# IRSensorController.net
KiCad netlist of a schematic drawn in EAGLE
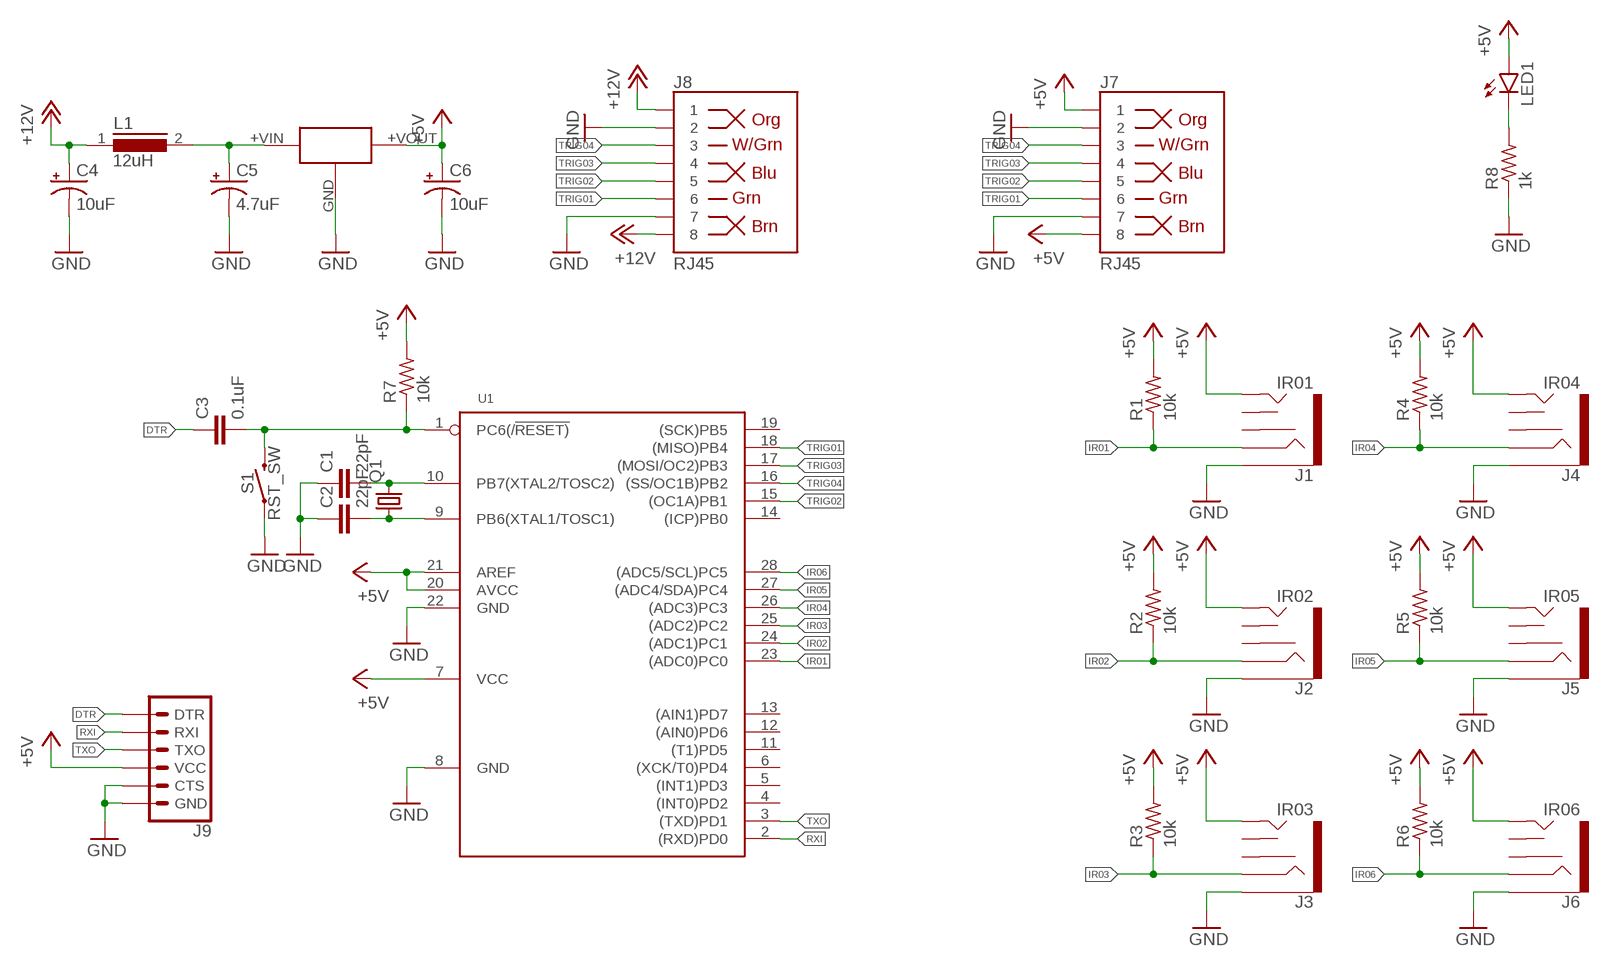
[diagram p0: schematic, sheet 1]

(export (version "E")
  (design (tool "Eeschema 10.0.6"))
  (components
    (comp (ref "C1")
      (value "22pF")
      (footprint "eagle-import:C050-025X075")
      (libsource (lib "eagle-import") (part "C-EU050-025X075"))
    )
    (comp (ref "C2")
      (value "22pF")
      (footprint "eagle-import:C050-025X075")
      (libsource (lib "eagle-import") (part "C-EU050-025X075"))
    )
    (comp (ref "C3")
      (value "0.1uF")
      (footprint "eagle-import:C050-025X075")
      (libsource (lib "eagle-import") (part "C-EU050-025X075"))
    )
    (comp (ref "C4")
      (value "10uF")
      (footprint "eagle-import:E3,5-8")
      (libsource (lib "eagle-import") (part "CPOL-USE3.5-8"))
    )
    (comp (ref "C5")
      (value "4.7uF")
      (footprint "eagle-import:E2,5-7")
      (libsource (lib "eagle-import") (part "CPOL-USE2.5-7"))
    )
    (comp (ref "C6")
      (value "10uF")
      (footprint "eagle-import:E3,5-8")
      (libsource (lib "eagle-import") (part "CPOL-USE3.5-8"))
    )
    (comp (ref "J1")
      (value "IR01")
      (footprint "eagle-import:AUDIO-JACK-KIT")
      (libsource (lib "eagle-import") (part "AUDIO_JACK_3.5MM_KIT"))
    )
    (comp (ref "J2")
      (value "IR02")
      (footprint "eagle-import:AUDIO-JACK-KIT")
      (libsource (lib "eagle-import") (part "AUDIO_JACK_3.5MM_KIT"))
    )
    (comp (ref "J3")
      (value "IR03")
      (footprint "eagle-import:AUDIO-JACK-KIT")
      (libsource (lib "eagle-import") (part "AUDIO_JACK_3.5MM_KIT"))
    )
    (comp (ref "J4")
      (value "IR04")
      (footprint "eagle-import:AUDIO-JACK-KIT")
      (libsource (lib "eagle-import") (part "AUDIO_JACK_3.5MM_KIT"))
    )
    (comp (ref "J5")
      (value "IR05")
      (footprint "eagle-import:AUDIO-JACK-KIT")
      (libsource (lib "eagle-import") (part "AUDIO_JACK_3.5MM_KIT"))
    )
    (comp (ref "J6")
      (value "IR06")
      (footprint "eagle-import:AUDIO-JACK-KIT")
      (libsource (lib "eagle-import") (part "AUDIO_JACK_3.5MM_KIT"))
    )
    (comp (ref "J7")
      (value "RJ45")
      (footprint "eagle-import:RJ45-8")
      (libsource (lib "eagle-import") (part "RJ45-8"))
    )
    (comp (ref "J8")
      (value "RJ45")
      (footprint "eagle-import:RJ45-8")
      (libsource (lib "eagle-import") (part "RJ45-8"))
    )
    (comp (ref "J9")
      (value "6_PIN_SERIAL_TARGETSILK")
      (footprint "eagle-import:6_PIN_SERIAL_TARGET_SIDE_W_SILK")
      (libsource (lib "eagle-import") (part "6_PIN_SERIAL_TARGETSILK"))
    )
    (comp (ref "L1")
      (value "12uH")
      (footprint "eagle-import:SUKW1-17")
      (libsource (lib "eagle-import") (part "B82131"))
    )
    (comp (ref "LED1")
      (value "LED5MM")
      (footprint "eagle-import:LED5MM")
      (libsource (lib "eagle-import") (part "LED5MM"))
    )
    (comp (ref "Q1")
      (value "CRYSTALHC49S")
      (footprint "eagle-import:HC49_S")
      (libsource (lib "eagle-import") (part "CRYSTALHC49S"))
    )
    (comp (ref "R1")
      (value "10k")
      (footprint "eagle-import:0204_7")
      (libsource (lib "eagle-import") (part "R-US_0204/7"))
    )
    (comp (ref "R2")
      (value "10k")
      (footprint "eagle-import:0204_7")
      (libsource (lib "eagle-import") (part "R-US_0204/7"))
    )
    (comp (ref "R3")
      (value "10k")
      (footprint "eagle-import:0204_7")
      (libsource (lib "eagle-import") (part "R-US_0204/7"))
    )
    (comp (ref "R4")
      (value "10k")
      (footprint "eagle-import:0204_7")
      (libsource (lib "eagle-import") (part "R-US_0204/7"))
    )
    (comp (ref "R5")
      (value "10k")
      (footprint "eagle-import:0204_7")
      (libsource (lib "eagle-import") (part "R-US_0204/7"))
    )
    (comp (ref "R6")
      (value "10k")
      (footprint "eagle-import:0204_7")
      (libsource (lib "eagle-import") (part "R-US_0204/7"))
    )
    (comp (ref "R7")
      (value "10k")
      (footprint "eagle-import:0204_7")
      (libsource (lib "eagle-import") (part "R-US_0204/7"))
    )
    (comp (ref "R8")
      (value "1k")
      (footprint "eagle-import:0204_7")
      (libsource (lib "eagle-import") (part "R-US_0204/7"))
    )
    (comp (ref "S1")
      (value "RST_SW")
      (footprint "eagle-import:TACTILE_SWITCH_PTH_6.0MM")
      (libsource (lib "eagle-import") (part "MOMENTARY-SWITCH-SPST-PTH-6.0MM"))
    )
    (comp (ref "U$1")
      (value "R_78E_5V")
      (footprint "eagle-import:R_78E")
      (libsource (lib "eagle-import") (part "R_78E_5V"))
    )
    (comp (ref "U1")
      (value "MCU-ATMEGA328P-PU(DIP28)")
      (footprint "eagle-import:DIP28-2.54-34.7X7.62MM")
      (fields (field (name "MPN") "ATMEGA328P-PU"))
      (libsource (lib "eagle-import") (part "MCU-ATMEGA328P-PU(DIP28)"))
    )
  )
  (nets
    (net (code "1") (name "+5V") (class "Default")
      (node (ref "C6") (pin "+") (pinfunction "+_+") (pintype "passive"))
      (node (ref "J1") (pin "TIP") (pinfunction "TIP_TIP") (pintype "bidirectional"))
      (node (ref "J2") (pin "TIP") (pinfunction "TIP_TIP") (pintype "bidirectional"))
      (node (ref "J3") (pin "TIP") (pinfunction "TIP_TIP") (pintype "bidirectional"))
      (node (ref "J4") (pin "TIP") (pinfunction "TIP_TIP") (pintype "bidirectional"))
      (node (ref "J5") (pin "TIP") (pinfunction "TIP_TIP") (pintype "bidirectional"))
      (node (ref "J6") (pin "TIP") (pinfunction "TIP_TIP") (pintype "bidirectional"))
      (node (ref "J7") (pin "1") (pinfunction "1_1") (pintype "bidirectional"))
      (node (ref "J7") (pin "8") (pinfunction "8_8") (pintype "bidirectional"))
      (node (ref "J9") (pin "P$4") (pinfunction "VCC_P$4") (pintype "passive"))
      (node (ref "LED1") (pin "A") (pinfunction "A_A") (pintype "passive"))
      (node (ref "R1") (pin "2") (pinfunction "2_2") (pintype "passive"))
      (node (ref "R2") (pin "2") (pinfunction "2_2") (pintype "passive"))
      (node (ref "R3") (pin "2") (pinfunction "2_2") (pintype "passive"))
      (node (ref "R4") (pin "2") (pinfunction "2_2") (pintype "passive"))
      (node (ref "R5") (pin "2") (pinfunction "2_2") (pintype "passive"))
      (node (ref "R6") (pin "2") (pinfunction "2_2") (pintype "passive"))
      (node (ref "R7") (pin "2") (pinfunction "2_2") (pintype "passive"))
      (node (ref "U$1") (pin "+VOUT") (pinfunction "+VOUT_+VOUT") (pintype "bidirectional"))
      (node (ref "U1") (pin "20") (pinfunction "AVCC_20") (pintype "bidirectional"))
      (node (ref "U1") (pin "21") (pinfunction "AREF_21") (pintype "bidirectional"))
      (node (ref "U1") (pin "7") (pinfunction "VCC_7") (pintype "bidirectional"))
    )
    (net (code "2") (name "+12V") (class "Default")
      (node (ref "C4") (pin "+") (pinfunction "+_+") (pintype "passive"))
      (node (ref "J8") (pin "1") (pinfunction "1_1") (pintype "bidirectional"))
      (node (ref "J8") (pin "8") (pinfunction "8_8") (pintype "bidirectional"))
      (node (ref "L1") (pin "1") (pinfunction "1_1") (pintype "passive"))
    )
    (net (code "3") (name "DTR") (class "Default")
      (node (ref "C3") (pin "1") (pinfunction "1_1") (pintype "passive"))
      (node (ref "J9") (pin "P$1") (pinfunction "DTR_P$1") (pintype "passive"))
    )
    (net (code "4") (name "GND") (class "Default")
      (node (ref "C1") (pin "1") (pinfunction "1_1") (pintype "passive"))
      (node (ref "C2") (pin "1") (pinfunction "1_1") (pintype "passive"))
      (node (ref "C4") (pin "-") (pinfunction "-_-") (pintype "passive"))
      (node (ref "C5") (pin "-") (pinfunction "-_-") (pintype "passive"))
      (node (ref "C6") (pin "-") (pinfunction "-_-") (pintype "passive"))
      (node (ref "J1") (pin "SLEEVE") (pinfunction "SLEEVE_SLEEVE") (pintype "bidirectional"))
      (node (ref "J2") (pin "SLEEVE") (pinfunction "SLEEVE_SLEEVE") (pintype "bidirectional"))
      (node (ref "J3") (pin "SLEEVE") (pinfunction "SLEEVE_SLEEVE") (pintype "bidirectional"))
      (node (ref "J4") (pin "SLEEVE") (pinfunction "SLEEVE_SLEEVE") (pintype "bidirectional"))
      (node (ref "J5") (pin "SLEEVE") (pinfunction "SLEEVE_SLEEVE") (pintype "bidirectional"))
      (node (ref "J6") (pin "SLEEVE") (pinfunction "SLEEVE_SLEEVE") (pintype "bidirectional"))
      (node (ref "J7") (pin "2") (pinfunction "2_2") (pintype "bidirectional"))
      (node (ref "J7") (pin "7") (pinfunction "7_7") (pintype "bidirectional"))
      (node (ref "J8") (pin "2") (pinfunction "2_2") (pintype "bidirectional"))
      (node (ref "J8") (pin "7") (pinfunction "7_7") (pintype "bidirectional"))
      (node (ref "J9") (pin "P$5") (pinfunction "CTS_P$5") (pintype "passive"))
      (node (ref "J9") (pin "P$6") (pinfunction "GND_P$6") (pintype "passive"))
      (node (ref "R8") (pin "1") (pinfunction "1_1") (pintype "passive"))
      (node (ref "S1") (pin "1") (pinfunction "1_1") (pintype "passive"))
      (node (ref "U$1") (pin "GND") (pinfunction "GND_GND") (pintype "bidirectional"))
      (node (ref "U1") (pin "22") (pinfunction "GND_22") (pintype "bidirectional"))
      (node (ref "U1") (pin "8") (pinfunction "GND_8") (pintype "bidirectional"))
    )
    (net (code "5") (name "IR01") (class "Default")
      (node (ref "J1") (pin "RING") (pinfunction "RING_RING") (pintype "bidirectional"))
      (node (ref "R1") (pin "1") (pinfunction "1_1") (pintype "passive"))
      (node (ref "U1") (pin "23") (pinfunction "(ADC0)PC0_23") (pintype "bidirectional"))
    )
    (net (code "6") (name "IR02") (class "Default")
      (node (ref "J2") (pin "RING") (pinfunction "RING_RING") (pintype "bidirectional"))
      (node (ref "R2") (pin "1") (pinfunction "1_1") (pintype "passive"))
      (node (ref "U1") (pin "24") (pinfunction "(ADC1)PC1_24") (pintype "bidirectional"))
    )
    (net (code "7") (name "IR03") (class "Default")
      (node (ref "J3") (pin "RING") (pinfunction "RING_RING") (pintype "bidirectional"))
      (node (ref "R3") (pin "1") (pinfunction "1_1") (pintype "passive"))
      (node (ref "U1") (pin "25") (pinfunction "(ADC2)PC2_25") (pintype "bidirectional"))
    )
    (net (code "8") (name "IR04") (class "Default")
      (node (ref "J4") (pin "RING") (pinfunction "RING_RING") (pintype "bidirectional"))
      (node (ref "R4") (pin "1") (pinfunction "1_1") (pintype "passive"))
      (node (ref "U1") (pin "26") (pinfunction "(ADC3)PC3_26") (pintype "bidirectional"))
    )
    (net (code "9") (name "IR05") (class "Default")
      (node (ref "J5") (pin "RING") (pinfunction "RING_RING") (pintype "bidirectional"))
      (node (ref "R5") (pin "1") (pinfunction "1_1") (pintype "passive"))
      (node (ref "U1") (pin "27") (pinfunction "(ADC4/SDA)PC4_27") (pintype "bidirectional"))
    )
    (net (code "10") (name "IR06") (class "Default")
      (node (ref "J6") (pin "RING") (pinfunction "RING_RING") (pintype "bidirectional"))
      (node (ref "R6") (pin "1") (pinfunction "1_1") (pintype "passive"))
      (node (ref "U1") (pin "28") (pinfunction "(ADC5/SCL)PC5_28") (pintype "bidirectional"))
    )
    (net (code "11") (name "Net-(C5-Pad+)") (class "Default")
      (node (ref "C5") (pin "+") (pinfunction "+_+") (pintype "passive"))
      (node (ref "L1") (pin "2") (pinfunction "2_2") (pintype "passive"))
      (node (ref "U$1") (pin "+VIN") (pinfunction "+VIN_+VIN") (pintype "bidirectional"))
    )
    (net (code "12") (name "Net-(LED1-C)") (class "Default")
      (node (ref "LED1") (pin "K") (pinfunction "C_K") (pintype "passive"))
      (node (ref "R8") (pin "2") (pinfunction "2_2") (pintype "passive"))
    )
    (net (code "13") (name "Net-(S1-2)") (class "Default")
      (node (ref "C3") (pin "2") (pinfunction "2_2") (pintype "passive"))
      (node (ref "R7") (pin "1") (pinfunction "1_1") (pintype "passive"))
      (node (ref "S1") (pin "3") (pinfunction "2_3") (pintype "passive"))
      (node (ref "U1") (pin "1") (pinfunction "PC6(/~{RESET})_1") (pintype "bidirectional"))
    )
    (net (code "14") (name "Net-(U1-PB6(XTAL1{slash}TOSC1))") (class "Default")
      (node (ref "C2") (pin "2") (pinfunction "2_2") (pintype "passive"))
      (node (ref "Q1") (pin "1") (pinfunction "1_1") (pintype "passive"))
      (node (ref "U1") (pin "9") (pinfunction "PB6(XTAL1/TOSC1)_9") (pintype "bidirectional"))
    )
    (net (code "15") (name "Net-(U1-PB7(XTAL2{slash}TOSC2))") (class "Default")
      (node (ref "C1") (pin "2") (pinfunction "2_2") (pintype "passive"))
      (node (ref "Q1") (pin "2") (pinfunction "2_2") (pintype "passive"))
      (node (ref "U1") (pin "10") (pinfunction "PB7(XTAL2/TOSC2)_10") (pintype "bidirectional"))
    )
    (net (code "16") (name "RXI") (class "Default")
      (node (ref "J9") (pin "P$3") (pinfunction "RXI_P$3") (pintype "passive"))
      (node (ref "U1") (pin "2") (pinfunction "(RXD)PD0_2") (pintype "bidirectional"))
    )
    (net (code "17") (name "TRIG01") (class "Default")
      (node (ref "J7") (pin "6") (pinfunction "6_6") (pintype "bidirectional"))
      (node (ref "J8") (pin "6") (pinfunction "6_6") (pintype "bidirectional"))
      (node (ref "U1") (pin "18") (pinfunction "(MISO)PB4_18") (pintype "bidirectional"))
    )
    (net (code "18") (name "TRIG02") (class "Default")
      (node (ref "J7") (pin "5") (pinfunction "5_5") (pintype "bidirectional"))
      (node (ref "J8") (pin "5") (pinfunction "5_5") (pintype "bidirectional"))
      (node (ref "U1") (pin "15") (pinfunction "(OC1A)PB1_15") (pintype "bidirectional"))
    )
    (net (code "19") (name "TRIG03") (class "Default")
      (node (ref "J7") (pin "4") (pinfunction "4_4") (pintype "bidirectional"))
      (node (ref "J8") (pin "4") (pinfunction "4_4") (pintype "bidirectional"))
      (node (ref "U1") (pin "17") (pinfunction "(MOSI/OC2)PB3_17") (pintype "bidirectional"))
    )
    (net (code "20") (name "TRIG04") (class "Default")
      (node (ref "J7") (pin "3") (pinfunction "3_3") (pintype "bidirectional"))
      (node (ref "J8") (pin "3") (pinfunction "3_3") (pintype "bidirectional"))
      (node (ref "U1") (pin "16") (pinfunction "(SS/OC1B)PB2_16") (pintype "bidirectional"))
    )
    (net (code "21") (name "TXO") (class "Default")
      (node (ref "J9") (pin "P$2") (pinfunction "TXO_P$2") (pintype "passive"))
      (node (ref "U1") (pin "3") (pinfunction "(TXD)PD1_3") (pintype "bidirectional"))
    )
    (net (code "22") (name "unconnected-(J1-PadRSH)") (class "Default")
      (node (ref "J1") (pin "RSH") (pinfunction "RSH_RSH") (pintype "bidirectional"))
    )
    (net (code "23") (name "unconnected-(J1-PadTSH)") (class "Default")
      (node (ref "J1") (pin "TSH") (pinfunction "TSH_TSH") (pintype "bidirectional"))
    )
    (net (code "24") (name "unconnected-(J2-PadRSH)") (class "Default")
      (node (ref "J2") (pin "RSH") (pinfunction "RSH_RSH") (pintype "bidirectional"))
    )
    (net (code "25") (name "unconnected-(J2-PadTSH)") (class "Default")
      (node (ref "J2") (pin "TSH") (pinfunction "TSH_TSH") (pintype "bidirectional"))
    )
    (net (code "26") (name "unconnected-(J3-PadRSH)") (class "Default")
      (node (ref "J3") (pin "RSH") (pinfunction "RSH_RSH") (pintype "bidirectional"))
    )
    (net (code "27") (name "unconnected-(J3-PadTSH)") (class "Default")
      (node (ref "J3") (pin "TSH") (pinfunction "TSH_TSH") (pintype "bidirectional"))
    )
    (net (code "28") (name "unconnected-(J4-PadRSH)") (class "Default")
      (node (ref "J4") (pin "RSH") (pinfunction "RSH_RSH") (pintype "bidirectional"))
    )
    (net (code "29") (name "unconnected-(J4-PadTSH)") (class "Default")
      (node (ref "J4") (pin "TSH") (pinfunction "TSH_TSH") (pintype "bidirectional"))
    )
    (net (code "30") (name "unconnected-(J5-PadRSH)") (class "Default")
      (node (ref "J5") (pin "RSH") (pinfunction "RSH_RSH") (pintype "bidirectional"))
    )
    (net (code "31") (name "unconnected-(J5-PadTSH)") (class "Default")
      (node (ref "J5") (pin "TSH") (pinfunction "TSH_TSH") (pintype "bidirectional"))
    )
    (net (code "32") (name "unconnected-(J6-PadRSH)") (class "Default")
      (node (ref "J6") (pin "RSH") (pinfunction "RSH_RSH") (pintype "bidirectional"))
    )
    (net (code "33") (name "unconnected-(J6-PadTSH)") (class "Default")
      (node (ref "J6") (pin "TSH") (pinfunction "TSH_TSH") (pintype "bidirectional"))
    )
    (net (code "34") (name "unconnected-(U1-(AIN0)PD6-Pad12)") (class "Default")
      (node (ref "U1") (pin "12") (pinfunction "(AIN0)PD6_12") (pintype "bidirectional"))
    )
    (net (code "35") (name "unconnected-(U1-(AIN1)PD7-Pad13)") (class "Default")
      (node (ref "U1") (pin "13") (pinfunction "(AIN1)PD7_13") (pintype "bidirectional"))
    )
    (net (code "36") (name "unconnected-(U1-(ICP)PB0-Pad14)") (class "Default")
      (node (ref "U1") (pin "14") (pinfunction "(ICP)PB0_14") (pintype "bidirectional"))
    )
    (net (code "37") (name "unconnected-(U1-(INT0)PD2-Pad4)") (class "Default")
      (node (ref "U1") (pin "4") (pinfunction "(INT0)PD2_4") (pintype "bidirectional"))
    )
    (net (code "38") (name "unconnected-(U1-(INT1)PD3-Pad5)") (class "Default")
      (node (ref "U1") (pin "5") (pinfunction "(INT1)PD3_5") (pintype "bidirectional"))
    )
    (net (code "39") (name "unconnected-(U1-(SCK)PB5-Pad19)") (class "Default")
      (node (ref "U1") (pin "19") (pinfunction "(SCK)PB5_19") (pintype "bidirectional"))
    )
    (net (code "40") (name "unconnected-(U1-(T1)PD5-Pad11)") (class "Default")
      (node (ref "U1") (pin "11") (pinfunction "(T1)PD5_11") (pintype "bidirectional"))
    )
    (net (code "41") (name "unconnected-(U1-(XCK{slash}T0)PD4-Pad6)") (class "Default")
      (node (ref "U1") (pin "6") (pinfunction "(XCK/T0)PD4_6") (pintype "bidirectional"))
    )
  )
)
